# 02-MIC.net
KiCad netlist of a schematic drawn in Altium Designer
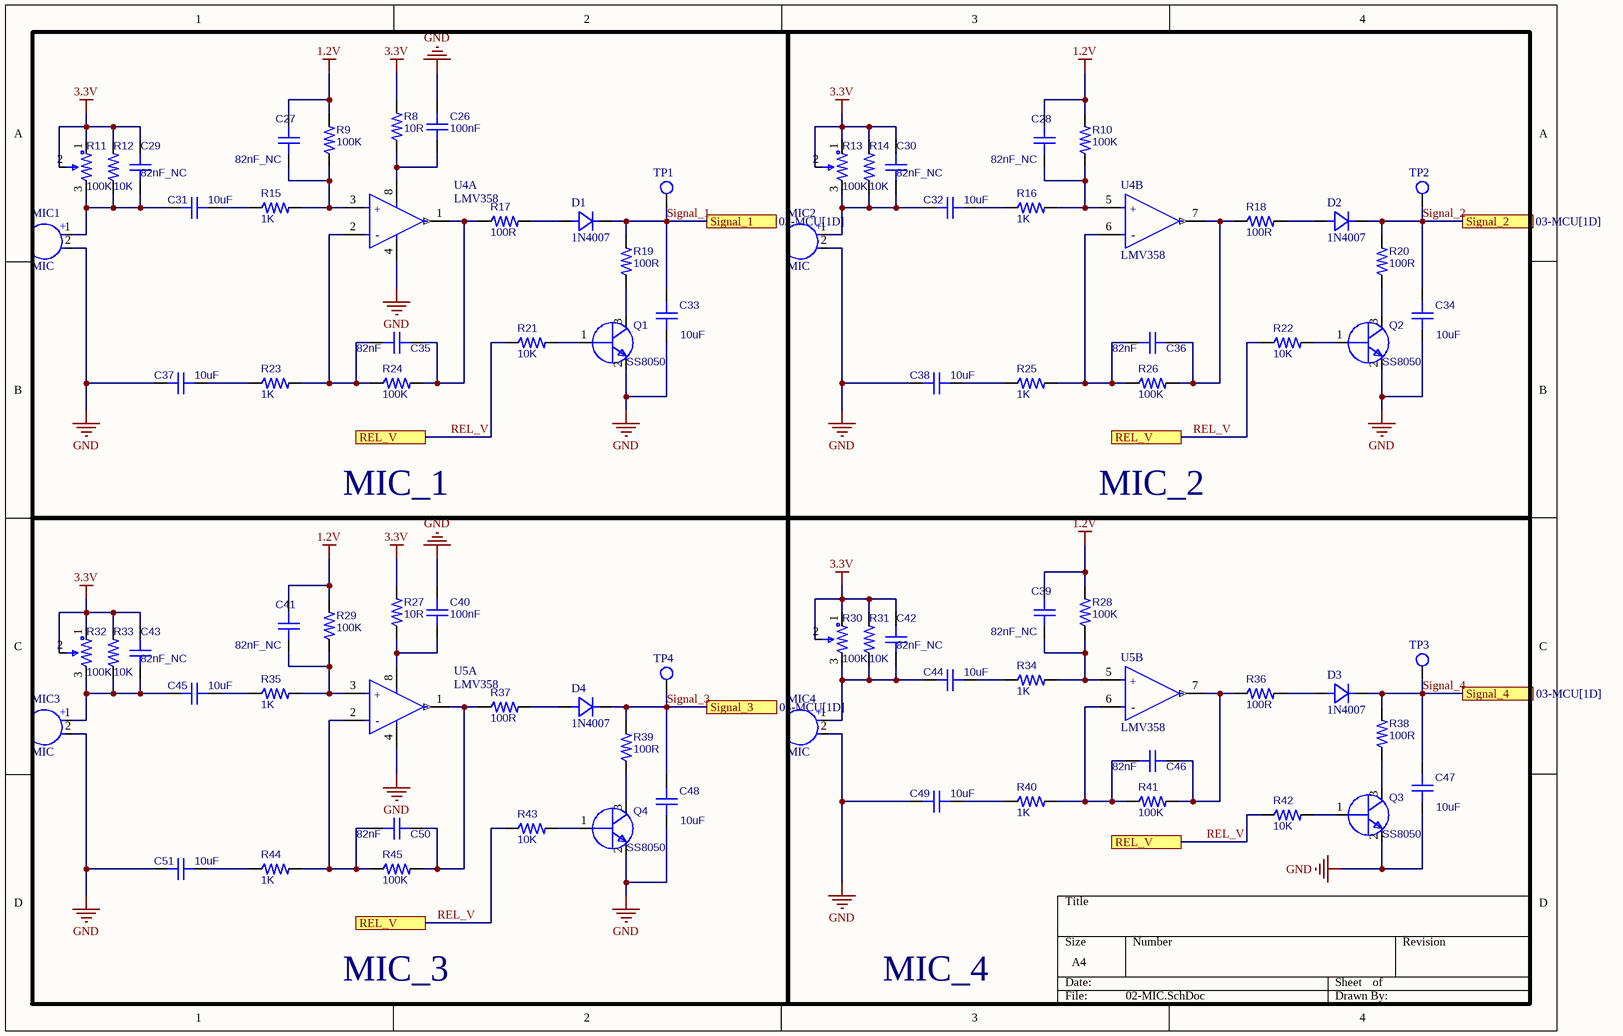
[diagram p0: 02-MIC.SchDoc]

(export (version "E")
  (design (tool "Eeschema 10.0.6"))
  (components
    (comp (ref "C26")
      (value "100nF")
      (footprint "CAP-SMD-0603")
      (description "贴片电容")
      (fields
        (field (name "BOM_MANUFACTURER PART") "CL03A104KQ3NNNC")
        (field (name "BOM_SUPPLIER PART") "C160831")
        (field (name "CONTRIBUTOR") "LCSC")
      )
      (libsource (lib "声源跟踪小车原理图库") (part "CAP"))
    )
    (comp (ref "C27")
      (value "82nF_NC")
      (footprint "CAP-SMD-0603")
      (description "贴片电容")
      (fields
        (field (name "BOM_MANUFACTURER PART") "CL03A104KQ3NNNC")
        (field (name "BOM_SUPPLIER PART") "C160831")
        (field (name "CONTRIBUTOR") "LCSC")
      )
      (libsource (lib "声源跟踪小车原理图库") (part "CAP"))
    )
    (comp (ref "C28")
      (value "82nF_NC")
      (footprint "CAP-SMD-0603")
      (description "贴片电容")
      (fields
        (field (name "BOM_MANUFACTURER PART") "CL03A104KQ3NNNC")
        (field (name "BOM_SUPPLIER PART") "C160831")
        (field (name "CONTRIBUTOR") "LCSC")
      )
      (libsource (lib "声源跟踪小车原理图库") (part "CAP"))
    )
    (comp (ref "C29")
      (value "82nF_NC")
      (footprint "CAP-SMD-0603")
      (description "贴片电容")
      (fields
        (field (name "BOM_MANUFACTURER PART") "CL03A104KQ3NNNC")
        (field (name "BOM_SUPPLIER PART") "C160831")
        (field (name "CONTRIBUTOR") "LCSC")
      )
      (libsource (lib "声源跟踪小车原理图库") (part "CAP"))
    )
    (comp (ref "C30")
      (value "82nF_NC")
      (footprint "CAP-SMD-0603")
      (description "贴片电容")
      (fields
        (field (name "BOM_MANUFACTURER PART") "CL03A104KQ3NNNC")
        (field (name "BOM_SUPPLIER PART") "C160831")
        (field (name "CONTRIBUTOR") "LCSC")
      )
      (libsource (lib "声源跟踪小车原理图库") (part "CAP"))
    )
    (comp (ref "C31")
      (value "10uF")
      (footprint "CAP-SMD-0603")
      (description "贴片电容")
      (fields
        (field (name "BOM_MANUFACTURER PART") "CL03A104KQ3NNNC")
        (field (name "BOM_SUPPLIER PART") "C160831")
        (field (name "CONTRIBUTOR") "LCSC")
      )
      (libsource (lib "声源跟踪小车原理图库") (part "CAP"))
    )
    (comp (ref "C32")
      (value "10uF")
      (footprint "CAP-SMD-0603")
      (description "贴片电容")
      (fields
        (field (name "BOM_MANUFACTURER PART") "CL03A104KQ3NNNC")
        (field (name "BOM_SUPPLIER PART") "C160831")
        (field (name "CONTRIBUTOR") "LCSC")
      )
      (libsource (lib "声源跟踪小车原理图库") (part "CAP"))
    )
    (comp (ref "C33")
      (value "10uF")
      (footprint "CAP-SMD-0603")
      (description "贴片电容")
      (fields
        (field (name "BOM_MANUFACTURER PART") "CL03A104KQ3NNNC")
        (field (name "BOM_SUPPLIER PART") "C160831")
        (field (name "CONTRIBUTOR") "LCSC")
      )
      (libsource (lib "声源跟踪小车原理图库") (part "CAP"))
    )
    (comp (ref "C34")
      (value "10uF")
      (footprint "CAP-SMD-0603")
      (description "贴片电容")
      (fields
        (field (name "BOM_MANUFACTURER PART") "CL03A104KQ3NNNC")
        (field (name "BOM_SUPPLIER PART") "C160831")
        (field (name "CONTRIBUTOR") "LCSC")
      )
      (libsource (lib "声源跟踪小车原理图库") (part "CAP"))
    )
    (comp (ref "C35")
      (value "82nF")
      (footprint "CAP-SMD-0603")
      (description "贴片电容")
      (fields
        (field (name "BOM_MANUFACTURER PART") "CL03A104KQ3NNNC")
        (field (name "BOM_SUPPLIER PART") "C160831")
        (field (name "CONTRIBUTOR") "LCSC")
      )
      (libsource (lib "声源跟踪小车原理图库") (part "CAP"))
    )
    (comp (ref "C36")
      (value "82nF")
      (footprint "CAP-SMD-0603")
      (description "贴片电容")
      (fields
        (field (name "BOM_MANUFACTURER PART") "CL03A104KQ3NNNC")
        (field (name "BOM_SUPPLIER PART") "C160831")
        (field (name "CONTRIBUTOR") "LCSC")
      )
      (libsource (lib "声源跟踪小车原理图库") (part "CAP"))
    )
    (comp (ref "C37")
      (value "10uF")
      (footprint "CAP-SMD-0603")
      (description "贴片电容")
      (fields
        (field (name "BOM_MANUFACTURER PART") "CL03A104KQ3NNNC")
        (field (name "BOM_SUPPLIER PART") "C160831")
        (field (name "CONTRIBUTOR") "LCSC")
      )
      (libsource (lib "声源跟踪小车原理图库") (part "CAP"))
    )
    (comp (ref "C38")
      (value "10uF")
      (footprint "CAP-SMD-0603")
      (description "贴片电容")
      (fields
        (field (name "BOM_MANUFACTURER PART") "CL03A104KQ3NNNC")
        (field (name "BOM_SUPPLIER PART") "C160831")
        (field (name "CONTRIBUTOR") "LCSC")
      )
      (libsource (lib "声源跟踪小车原理图库") (part "CAP"))
    )
    (comp (ref "C39")
      (value "82nF_NC")
      (footprint "CAP-SMD-0603")
      (description "贴片电容")
      (fields
        (field (name "BOM_MANUFACTURER PART") "CL03A104KQ3NNNC")
        (field (name "BOM_SUPPLIER PART") "C160831")
        (field (name "CONTRIBUTOR") "LCSC")
      )
      (libsource (lib "声源跟踪小车原理图库") (part "CAP"))
    )
    (comp (ref "C40")
      (value "100nF")
      (footprint "CAP-SMD-0603")
      (description "贴片电容")
      (fields
        (field (name "BOM_MANUFACTURER PART") "CL03A104KQ3NNNC")
        (field (name "BOM_SUPPLIER PART") "C160831")
        (field (name "CONTRIBUTOR") "LCSC")
      )
      (libsource (lib "声源跟踪小车原理图库") (part "CAP"))
    )
    (comp (ref "C41")
      (value "82nF_NC")
      (footprint "CAP-SMD-0603")
      (description "贴片电容")
      (fields
        (field (name "BOM_MANUFACTURER PART") "CL03A104KQ3NNNC")
        (field (name "BOM_SUPPLIER PART") "C160831")
        (field (name "CONTRIBUTOR") "LCSC")
      )
      (libsource (lib "声源跟踪小车原理图库") (part "CAP"))
    )
    (comp (ref "C42")
      (value "82nF_NC")
      (footprint "CAP-SMD-0603")
      (description "贴片电容")
      (fields
        (field (name "BOM_MANUFACTURER PART") "CL03A104KQ3NNNC")
        (field (name "BOM_SUPPLIER PART") "C160831")
        (field (name "CONTRIBUTOR") "LCSC")
      )
      (libsource (lib "声源跟踪小车原理图库") (part "CAP"))
    )
    (comp (ref "C43")
      (value "82nF_NC")
      (footprint "CAP-SMD-0603")
      (description "贴片电容")
      (fields
        (field (name "BOM_MANUFACTURER PART") "CL03A104KQ3NNNC")
        (field (name "BOM_SUPPLIER PART") "C160831")
        (field (name "CONTRIBUTOR") "LCSC")
      )
      (libsource (lib "声源跟踪小车原理图库") (part "CAP"))
    )
    (comp (ref "C44")
      (value "10uF")
      (footprint "CAP-SMD-0603")
      (description "贴片电容")
      (fields
        (field (name "BOM_MANUFACTURER PART") "CL03A104KQ3NNNC")
        (field (name "BOM_SUPPLIER PART") "C160831")
        (field (name "CONTRIBUTOR") "LCSC")
      )
      (libsource (lib "声源跟踪小车原理图库") (part "CAP"))
    )
    (comp (ref "C45")
      (value "10uF")
      (footprint "CAP-SMD-0603")
      (description "贴片电容")
      (fields
        (field (name "BOM_MANUFACTURER PART") "CL03A104KQ3NNNC")
        (field (name "BOM_SUPPLIER PART") "C160831")
        (field (name "CONTRIBUTOR") "LCSC")
      )
      (libsource (lib "声源跟踪小车原理图库") (part "CAP"))
    )
    (comp (ref "C46")
      (value "82nF")
      (footprint "CAP-SMD-0603")
      (description "贴片电容")
      (fields
        (field (name "BOM_MANUFACTURER PART") "CL03A104KQ3NNNC")
        (field (name "BOM_SUPPLIER PART") "C160831")
        (field (name "CONTRIBUTOR") "LCSC")
      )
      (libsource (lib "声源跟踪小车原理图库") (part "CAP"))
    )
    (comp (ref "C47")
      (value "10uF")
      (footprint "CAP-SMD-0603")
      (description "贴片电容")
      (fields
        (field (name "BOM_MANUFACTURER PART") "CL03A104KQ3NNNC")
        (field (name "BOM_SUPPLIER PART") "C160831")
        (field (name "CONTRIBUTOR") "LCSC")
      )
      (libsource (lib "声源跟踪小车原理图库") (part "CAP"))
    )
    (comp (ref "C48")
      (value "10uF")
      (footprint "CAP-SMD-0603")
      (description "贴片电容")
      (fields
        (field (name "BOM_MANUFACTURER PART") "CL03A104KQ3NNNC")
        (field (name "BOM_SUPPLIER PART") "C160831")
        (field (name "CONTRIBUTOR") "LCSC")
      )
      (libsource (lib "声源跟踪小车原理图库") (part "CAP"))
    )
    (comp (ref "C49")
      (value "10uF")
      (footprint "CAP-SMD-0603")
      (description "贴片电容")
      (fields
        (field (name "BOM_MANUFACTURER PART") "CL03A104KQ3NNNC")
        (field (name "BOM_SUPPLIER PART") "C160831")
        (field (name "CONTRIBUTOR") "LCSC")
      )
      (libsource (lib "声源跟踪小车原理图库") (part "CAP"))
    )
    (comp (ref "C50")
      (value "82nF")
      (footprint "CAP-SMD-0603")
      (description "贴片电容")
      (fields
        (field (name "BOM_MANUFACTURER PART") "CL03A104KQ3NNNC")
        (field (name "BOM_SUPPLIER PART") "C160831")
        (field (name "CONTRIBUTOR") "LCSC")
      )
      (libsource (lib "声源跟踪小车原理图库") (part "CAP"))
    )
    (comp (ref "C51")
      (value "10uF")
      (footprint "CAP-SMD-0603")
      (description "贴片电容")
      (fields
        (field (name "BOM_MANUFACTURER PART") "CL03A104KQ3NNNC")
        (field (name "BOM_SUPPLIER PART") "C160831")
        (field (name "CONTRIBUTOR") "LCSC")
      )
      (libsource (lib "声源跟踪小车原理图库") (part "CAP"))
    )
    (comp (ref "D1")
      (value "1N4007")
      (footprint "SOD-123-P3.4")
      (description "二极管1N4148W")
      (fields (field (name "MANUFACTURER") "PSI(宝力芯)") (field (name "MANUFACTURER PART") "1N4148W"))
      (libsource (lib "声源跟踪小车原理图库") (part "Diode"))
    )
    (comp (ref "D2")
      (value "1N4007")
      (footprint "SOD-123-P3.4")
      (description "二极管1N4148W")
      (fields (field (name "MANUFACTURER") "PSI(宝力芯)") (field (name "MANUFACTURER PART") "1N4148W"))
      (libsource (lib "声源跟踪小车原理图库") (part "Diode"))
    )
    (comp (ref "D3")
      (value "1N4007")
      (footprint "SOD-123-P3.4")
      (description "二极管1N4148W")
      (fields (field (name "MANUFACTURER") "PSI(宝力芯)") (field (name "MANUFACTURER PART") "1N4148W"))
      (libsource (lib "声源跟踪小车原理图库") (part "Diode"))
    )
    (comp (ref "D4")
      (value "1N4007")
      (footprint "SOD-123-P3.4")
      (description "二极管1N4148W")
      (fields (field (name "MANUFACTURER") "PSI(宝力芯)") (field (name "MANUFACTURER PART") "1N4148W"))
      (libsource (lib "声源跟踪小车原理图库") (part "Diode"))
    )
    (comp (ref "MIC1")
      (value "MIC")
      (footprint "CONN-TH-1X2P-P2.54_2")
      (description "咪头MIC COND ANALOG OMNI -38DB")
      (libsource (lib "声源跟踪小车原理图库") (part "MIC"))
    )
    (comp (ref "MIC2")
      (value "MIC")
      (footprint "CONN-TH-1X2P-P2.54_2")
      (description "咪头MIC COND ANALOG OMNI -38DB")
      (libsource (lib "声源跟踪小车原理图库") (part "MIC"))
    )
    (comp (ref "MIC3")
      (value "MIC")
      (footprint "CONN-TH-1X2P-P2.54_2")
      (description "咪头MIC COND ANALOG OMNI -38DB")
      (libsource (lib "声源跟踪小车原理图库") (part "MIC"))
    )
    (comp (ref "MIC4")
      (value "MIC")
      (footprint "CONN-TH-1X2P-P2.54_2")
      (description "咪头MIC COND ANALOG OMNI -38DB")
      (libsource (lib "声源跟踪小车原理图库") (part "MIC"))
    )
    (comp (ref "Q1")
      (value "SS8050")
      (footprint "SOT-23-3-LP2.28-P1.91")
      (description "贴片NPN三极管")
      (fields
        (field (name "BOM_SUPPLIER PART") "C2898668")
        (field (name "BOM_MANUFACTURER PART") "S9013")
        (field (name "CONTRIBUTOR") "LCSC")
      )
      (libsource (lib "声源跟踪小车原理图库") (part "NPN-SOT-23-3"))
    )
    (comp (ref "Q2")
      (value "SS8050")
      (footprint "SOT-23-3-LP2.28-P1.91")
      (description "贴片NPN三极管")
      (fields
        (field (name "BOM_SUPPLIER PART") "C2898668")
        (field (name "BOM_MANUFACTURER PART") "S9013")
        (field (name "CONTRIBUTOR") "LCSC")
      )
      (libsource (lib "声源跟踪小车原理图库") (part "NPN-SOT-23-3"))
    )
    (comp (ref "Q3")
      (value "SS8050")
      (footprint "SOT-23-3-LP2.28-P1.91")
      (description "贴片NPN三极管")
      (fields
        (field (name "BOM_SUPPLIER PART") "C2898668")
        (field (name "BOM_MANUFACTURER PART") "S9013")
        (field (name "CONTRIBUTOR") "LCSC")
      )
      (libsource (lib "声源跟踪小车原理图库") (part "NPN-SOT-23-3"))
    )
    (comp (ref "Q4")
      (value "SS8050")
      (footprint "SOT-23-3-LP2.28-P1.91")
      (description "贴片NPN三极管")
      (fields
        (field (name "BOM_SUPPLIER PART") "C2898668")
        (field (name "BOM_MANUFACTURER PART") "S9013")
        (field (name "CONTRIBUTOR") "LCSC")
      )
      (libsource (lib "声源跟踪小车原理图库") (part "NPN-SOT-23-3"))
    )
    (comp (ref "R8")
      (value "10R")
      (footprint "RES-SMD-0603")
      (description "贴片电阻")
      (fields
        (field (name "BOM_SUPPLIER PART") "C118966")
        (field (name "BOM_MANUFACTURER PART") "3362P-1-104")
        (field (name "CONTRIBUTOR") "LCSC")
      )
      (libsource (lib "声源跟踪小车原理图库") (part "RES"))
    )
    (comp (ref "R9")
      (value "100K")
      (footprint "RES-SMD-0603")
      (description "贴片电阻")
      (fields
        (field (name "BOM_SUPPLIER PART") "C118966")
        (field (name "BOM_MANUFACTURER PART") "3362P-1-104")
        (field (name "CONTRIBUTOR") "LCSC")
      )
      (libsource (lib "声源跟踪小车原理图库") (part "RES"))
    )
    (comp (ref "R10")
      (value "100K")
      (footprint "RES-SMD-0603")
      (description "贴片电阻")
      (fields
        (field (name "BOM_SUPPLIER PART") "C118966")
        (field (name "BOM_MANUFACTURER PART") "3362P-1-104")
        (field (name "CONTRIBUTOR") "LCSC")
      )
      (libsource (lib "声源跟踪小车原理图库") (part "RES"))
    )
    (comp (ref "R11")
      (value "100K")
      (footprint "RES-TH-ADJ-3396W")
      (description "可调电阻,电位器")
      (fields
        (field (name "BOM_SUPPLIER PART") "C118966")
        (field (name "BOM_MANUFACTURER PART") "3362P-1-104")
        (field (name "CONTRIBUTOR") "LCSC")
      )
      (libsource (lib "声源跟踪小车原理图库") (part "RES-ADJ"))
    )
    (comp (ref "R12")
      (value "10K")
      (footprint "RES-SMD-0603")
      (description "贴片电阻")
      (fields
        (field (name "BOM_SUPPLIER PART") "C118966")
        (field (name "BOM_MANUFACTURER PART") "3362P-1-104")
        (field (name "CONTRIBUTOR") "LCSC")
      )
      (libsource (lib "声源跟踪小车原理图库") (part "RES"))
    )
    (comp (ref "R13")
      (value "100K")
      (footprint "RES-TH-ADJ-3396W")
      (description "可调电阻,电位器")
      (fields
        (field (name "BOM_SUPPLIER PART") "C118966")
        (field (name "BOM_MANUFACTURER PART") "3362P-1-104")
        (field (name "CONTRIBUTOR") "LCSC")
      )
      (libsource (lib "声源跟踪小车原理图库") (part "RES-ADJ"))
    )
    (comp (ref "R14")
      (value "10K")
      (footprint "RES-SMD-0603")
      (description "贴片电阻")
      (fields
        (field (name "BOM_SUPPLIER PART") "C118966")
        (field (name "BOM_MANUFACTURER PART") "3362P-1-104")
        (field (name "CONTRIBUTOR") "LCSC")
      )
      (libsource (lib "声源跟踪小车原理图库") (part "RES"))
    )
    (comp (ref "R15")
      (value "1K")
      (footprint "RES-SMD-0603")
      (description "贴片电阻")
      (fields
        (field (name "BOM_SUPPLIER PART") "C118966")
        (field (name "BOM_MANUFACTURER PART") "3362P-1-104")
        (field (name "CONTRIBUTOR") "LCSC")
      )
      (libsource (lib "声源跟踪小车原理图库") (part "RES"))
    )
    (comp (ref "R16")
      (value "1K")
      (footprint "RES-SMD-0603")
      (description "贴片电阻")
      (fields
        (field (name "BOM_SUPPLIER PART") "C118966")
        (field (name "BOM_MANUFACTURER PART") "3362P-1-104")
        (field (name "CONTRIBUTOR") "LCSC")
      )
      (libsource (lib "声源跟踪小车原理图库") (part "RES"))
    )
    (comp (ref "R17")
      (value "100R")
      (footprint "RES-SMD-0603")
      (description "贴片电阻")
      (fields
        (field (name "BOM_SUPPLIER PART") "C118966")
        (field (name "BOM_MANUFACTURER PART") "3362P-1-104")
        (field (name "CONTRIBUTOR") "LCSC")
      )
      (libsource (lib "声源跟踪小车原理图库") (part "RES"))
    )
    (comp (ref "R18")
      (value "100R")
      (footprint "RES-SMD-0603")
      (description "贴片电阻")
      (fields
        (field (name "BOM_SUPPLIER PART") "C118966")
        (field (name "BOM_MANUFACTURER PART") "3362P-1-104")
        (field (name "CONTRIBUTOR") "LCSC")
      )
      (libsource (lib "声源跟踪小车原理图库") (part "RES"))
    )
    (comp (ref "R19")
      (value "100R")
      (footprint "RES-SMD-0603")
      (description "贴片电阻")
      (fields
        (field (name "BOM_SUPPLIER PART") "C118966")
        (field (name "BOM_MANUFACTURER PART") "3362P-1-104")
        (field (name "CONTRIBUTOR") "LCSC")
      )
      (libsource (lib "声源跟踪小车原理图库") (part "RES"))
    )
    (comp (ref "R20")
      (value "100R")
      (footprint "RES-SMD-0603")
      (description "贴片电阻")
      (fields
        (field (name "BOM_SUPPLIER PART") "C118966")
        (field (name "BOM_MANUFACTURER PART") "3362P-1-104")
        (field (name "CONTRIBUTOR") "LCSC")
      )
      (libsource (lib "声源跟踪小车原理图库") (part "RES"))
    )
    (comp (ref "R21")
      (value "10K")
      (footprint "RES-SMD-0603")
      (description "贴片电阻")
      (fields
        (field (name "BOM_SUPPLIER PART") "C118966")
        (field (name "BOM_MANUFACTURER PART") "3362P-1-104")
        (field (name "CONTRIBUTOR") "LCSC")
      )
      (libsource (lib "声源跟踪小车原理图库") (part "RES"))
    )
    (comp (ref "R22")
      (value "10K")
      (footprint "RES-SMD-0603")
      (description "贴片电阻")
      (fields
        (field (name "BOM_SUPPLIER PART") "C118966")
        (field (name "BOM_MANUFACTURER PART") "3362P-1-104")
        (field (name "CONTRIBUTOR") "LCSC")
      )
      (libsource (lib "声源跟踪小车原理图库") (part "RES"))
    )
    (comp (ref "R23")
      (value "1K")
      (footprint "RES-SMD-0603")
      (description "贴片电阻")
      (fields
        (field (name "BOM_SUPPLIER PART") "C118966")
        (field (name "BOM_MANUFACTURER PART") "3362P-1-104")
        (field (name "CONTRIBUTOR") "LCSC")
      )
      (libsource (lib "声源跟踪小车原理图库") (part "RES"))
    )
    (comp (ref "R24")
      (value "100K")
      (footprint "RES-SMD-0603")
      (description "贴片电阻")
      (fields
        (field (name "BOM_SUPPLIER PART") "C118966")
        (field (name "BOM_MANUFACTURER PART") "3362P-1-104")
        (field (name "CONTRIBUTOR") "LCSC")
      )
      (libsource (lib "声源跟踪小车原理图库") (part "RES"))
    )
    (comp (ref "R25")
      (value "1K")
      (footprint "RES-SMD-0603")
      (description "贴片电阻")
      (fields
        (field (name "BOM_SUPPLIER PART") "C118966")
        (field (name "BOM_MANUFACTURER PART") "3362P-1-104")
        (field (name "CONTRIBUTOR") "LCSC")
      )
      (libsource (lib "声源跟踪小车原理图库") (part "RES"))
    )
    (comp (ref "R26")
      (value "100K")
      (footprint "RES-SMD-0603")
      (description "贴片电阻")
      (fields
        (field (name "BOM_SUPPLIER PART") "C118966")
        (field (name "BOM_MANUFACTURER PART") "3362P-1-104")
        (field (name "CONTRIBUTOR") "LCSC")
      )
      (libsource (lib "声源跟踪小车原理图库") (part "RES"))
    )
    (comp (ref "R27")
      (value "10R")
      (footprint "RES-SMD-0603")
      (description "贴片电阻")
      (fields
        (field (name "BOM_SUPPLIER PART") "C118966")
        (field (name "BOM_MANUFACTURER PART") "3362P-1-104")
        (field (name "CONTRIBUTOR") "LCSC")
      )
      (libsource (lib "声源跟踪小车原理图库") (part "RES"))
    )
    (comp (ref "R28")
      (value "100K")
      (footprint "RES-SMD-0603")
      (description "贴片电阻")
      (fields
        (field (name "BOM_SUPPLIER PART") "C118966")
        (field (name "BOM_MANUFACTURER PART") "3362P-1-104")
        (field (name "CONTRIBUTOR") "LCSC")
      )
      (libsource (lib "声源跟踪小车原理图库") (part "RES"))
    )
    (comp (ref "R29")
      (value "100K")
      (footprint "RES-SMD-0603")
      (description "贴片电阻")
      (fields
        (field (name "BOM_SUPPLIER PART") "C118966")
        (field (name "BOM_MANUFACTURER PART") "3362P-1-104")
        (field (name "CONTRIBUTOR") "LCSC")
      )
      (libsource (lib "声源跟踪小车原理图库") (part "RES"))
    )
    (comp (ref "R30")
      (value "100K")
      (footprint "RES-TH-ADJ-3396W")
      (description "可调电阻,电位器")
      (fields
        (field (name "BOM_SUPPLIER PART") "C118966")
        (field (name "BOM_MANUFACTURER PART") "3362P-1-104")
        (field (name "CONTRIBUTOR") "LCSC")
      )
      (libsource (lib "声源跟踪小车原理图库") (part "RES-ADJ"))
    )
    (comp (ref "R31")
      (value "10K")
      (footprint "RES-SMD-0603")
      (description "贴片电阻")
      (fields
        (field (name "BOM_SUPPLIER PART") "C118966")
        (field (name "BOM_MANUFACTURER PART") "3362P-1-104")
        (field (name "CONTRIBUTOR") "LCSC")
      )
      (libsource (lib "声源跟踪小车原理图库") (part "RES"))
    )
    (comp (ref "R32")
      (value "100K")
      (footprint "RES-TH-ADJ-3396W")
      (description "可调电阻,电位器")
      (fields
        (field (name "BOM_SUPPLIER PART") "C118966")
        (field (name "BOM_MANUFACTURER PART") "3362P-1-104")
        (field (name "CONTRIBUTOR") "LCSC")
      )
      (libsource (lib "声源跟踪小车原理图库") (part "RES-ADJ"))
    )
    (comp (ref "R33")
      (value "10K")
      (footprint "RES-SMD-0603")
      (description "贴片电阻")
      (fields
        (field (name "BOM_SUPPLIER PART") "C118966")
        (field (name "BOM_MANUFACTURER PART") "3362P-1-104")
        (field (name "CONTRIBUTOR") "LCSC")
      )
      (libsource (lib "声源跟踪小车原理图库") (part "RES"))
    )
    (comp (ref "R34")
      (value "1K")
      (footprint "RES-SMD-0603")
      (description "贴片电阻")
      (fields
        (field (name "BOM_SUPPLIER PART") "C118966")
        (field (name "BOM_MANUFACTURER PART") "3362P-1-104")
        (field (name "CONTRIBUTOR") "LCSC")
      )
      (libsource (lib "声源跟踪小车原理图库") (part "RES"))
    )
    (comp (ref "R35")
      (value "1K")
      (footprint "RES-SMD-0603")
      (description "贴片电阻")
      (fields
        (field (name "BOM_SUPPLIER PART") "C118966")
        (field (name "BOM_MANUFACTURER PART") "3362P-1-104")
        (field (name "CONTRIBUTOR") "LCSC")
      )
      (libsource (lib "声源跟踪小车原理图库") (part "RES"))
    )
    (comp (ref "R36")
      (value "100R")
      (footprint "RES-SMD-0603")
      (description "贴片电阻")
      (fields
        (field (name "BOM_SUPPLIER PART") "C118966")
        (field (name "BOM_MANUFACTURER PART") "3362P-1-104")
        (field (name "CONTRIBUTOR") "LCSC")
      )
      (libsource (lib "声源跟踪小车原理图库") (part "RES"))
    )
    (comp (ref "R37")
      (value "100R")
      (footprint "RES-SMD-0603")
      (description "贴片电阻")
      (fields
        (field (name "BOM_SUPPLIER PART") "C118966")
        (field (name "BOM_MANUFACTURER PART") "3362P-1-104")
        (field (name "CONTRIBUTOR") "LCSC")
      )
      (libsource (lib "声源跟踪小车原理图库") (part "RES"))
    )
    (comp (ref "R38")
      (value "100R")
      (footprint "RES-SMD-0603")
      (description "贴片电阻")
      (fields
        (field (name "BOM_SUPPLIER PART") "C118966")
        (field (name "BOM_MANUFACTURER PART") "3362P-1-104")
        (field (name "CONTRIBUTOR") "LCSC")
      )
      (libsource (lib "声源跟踪小车原理图库") (part "RES"))
    )
    (comp (ref "R39")
      (value "100R")
      (footprint "RES-SMD-0603")
      (description "贴片电阻")
      (fields
        (field (name "BOM_SUPPLIER PART") "C118966")
        (field (name "BOM_MANUFACTURER PART") "3362P-1-104")
        (field (name "CONTRIBUTOR") "LCSC")
      )
      (libsource (lib "声源跟踪小车原理图库") (part "RES"))
    )
    (comp (ref "R40")
      (value "1K")
      (footprint "RES-SMD-0603")
      (description "贴片电阻")
      (fields
        (field (name "BOM_SUPPLIER PART") "C118966")
        (field (name "BOM_MANUFACTURER PART") "3362P-1-104")
        (field (name "CONTRIBUTOR") "LCSC")
      )
      (libsource (lib "声源跟踪小车原理图库") (part "RES"))
    )
    (comp (ref "R41")
      (value "100K")
      (footprint "RES-SMD-0603")
      (description "贴片电阻")
      (fields
        (field (name "BOM_SUPPLIER PART") "C118966")
        (field (name "BOM_MANUFACTURER PART") "3362P-1-104")
        (field (name "CONTRIBUTOR") "LCSC")
      )
      (libsource (lib "声源跟踪小车原理图库") (part "RES"))
    )
    (comp (ref "R42")
      (value "10K")
      (footprint "RES-SMD-0603")
      (description "贴片电阻")
      (fields
        (field (name "BOM_SUPPLIER PART") "C118966")
        (field (name "BOM_MANUFACTURER PART") "3362P-1-104")
        (field (name "CONTRIBUTOR") "LCSC")
      )
      (libsource (lib "声源跟踪小车原理图库") (part "RES"))
    )
    (comp (ref "R43")
      (value "10K")
      (footprint "RES-SMD-0603")
      (description "贴片电阻")
      (fields
        (field (name "BOM_SUPPLIER PART") "C118966")
        (field (name "BOM_MANUFACTURER PART") "3362P-1-104")
        (field (name "CONTRIBUTOR") "LCSC")
      )
      (libsource (lib "声源跟踪小车原理图库") (part "RES"))
    )
    (comp (ref "R44")
      (value "1K")
      (footprint "RES-SMD-0603")
      (description "贴片电阻")
      (fields
        (field (name "BOM_SUPPLIER PART") "C118966")
        (field (name "BOM_MANUFACTURER PART") "3362P-1-104")
        (field (name "CONTRIBUTOR") "LCSC")
      )
      (libsource (lib "声源跟踪小车原理图库") (part "RES"))
    )
    (comp (ref "R45")
      (value "100K")
      (footprint "RES-SMD-0603")
      (description "贴片电阻")
      (fields
        (field (name "BOM_SUPPLIER PART") "C118966")
        (field (name "BOM_MANUFACTURER PART") "3362P-1-104")
        (field (name "CONTRIBUTOR") "LCSC")
      )
      (libsource (lib "声源跟踪小车原理图库") (part "RES"))
    )
    (comp (ref "TP1")
      (value "TP")
      (footprint "TP")
      (description "TP测试点")
      (libsource (lib "声源跟踪小车原理图库") (part "TP"))
    )
    (comp (ref "TP2")
      (value "TP")
      (footprint "TP")
      (description "TP测试点")
      (libsource (lib "声源跟踪小车原理图库") (part "TP"))
    )
    (comp (ref "TP3")
      (value "TP")
      (footprint "TP")
      (description "TP测试点")
      (libsource (lib "声源跟踪小车原理图库") (part "TP"))
    )
    (comp (ref "TP4")
      (value "TP")
      (footprint "TP")
      (description "TP测试点")
      (libsource (lib "声源跟踪小车原理图库") (part "TP"))
    )
    (comp (ref "U4")
      (value "LMV358")
      (footprint "SOIC-8-LP5.5-P1.27")
      (description "运放IC OPAMP GP 2 CIRCUIT 8SOIC")
      (libsource (lib "声源跟踪小车原理图库") (part "LMV358"))
    )
    (comp (ref "U5")
      (value "LMV358")
      (footprint "SOIC-8-LP5.5-P1.27")
      (description "运放IC OPAMP GP 2 CIRCUIT 8SOIC")
      (libsource (lib "声源跟踪小车原理图库") (part "LMV358"))
    )
  )
  (nets
    (net (code "1") (name "/REL_V") (class "Default")
      (node (ref "R21") (pin "1") (pinfunction "1_1") (pintype "passive"))
      (node (ref "R22") (pin "1") (pinfunction "1_1") (pintype "passive"))
      (node (ref "R42") (pin "1") (pinfunction "1_1") (pintype "passive"))
      (node (ref "R43") (pin "1") (pinfunction "1_1") (pintype "passive"))
    )
    (net (code "2") (name "/Signal_1") (class "Default")
      (node (ref "C33") (pin "2") (pinfunction "2_2") (pintype "passive"))
      (node (ref "D1") (pin "2") (pinfunction "A_2") (pintype "passive"))
      (node (ref "R19") (pin "2") (pinfunction "2_2") (pintype "passive"))
      (node (ref "TP1") (pin "1") (pinfunction "1_1") (pintype "passive"))
    )
    (net (code "3") (name "/Signal_2") (class "Default")
      (node (ref "C34") (pin "2") (pinfunction "2_2") (pintype "passive"))
      (node (ref "D2") (pin "2") (pinfunction "A_2") (pintype "passive"))
      (node (ref "R20") (pin "2") (pinfunction "2_2") (pintype "passive"))
      (node (ref "TP2") (pin "1") (pinfunction "1_1") (pintype "passive"))
    )
    (net (code "4") (name "/Signal_3") (class "Default")
      (node (ref "C48") (pin "2") (pinfunction "2_2") (pintype "passive"))
      (node (ref "D4") (pin "2") (pinfunction "A_2") (pintype "passive"))
      (node (ref "R39") (pin "2") (pinfunction "2_2") (pintype "passive"))
      (node (ref "TP4") (pin "1") (pinfunction "1_1") (pintype "passive"))
    )
    (net (code "5") (name "/Signal_4") (class "Default")
      (node (ref "C47") (pin "2") (pinfunction "2_2") (pintype "passive"))
      (node (ref "D3") (pin "2") (pinfunction "A_2") (pintype "passive"))
      (node (ref "R38") (pin "2") (pinfunction "2_2") (pintype "passive"))
      (node (ref "TP3") (pin "1") (pinfunction "1_1") (pintype "passive"))
    )
    (net (code "6") (name "1.2V") (class "Default")
      (node (ref "C27") (pin "2") (pinfunction "2_2") (pintype "passive"))
      (node (ref "C28") (pin "2") (pinfunction "2_2") (pintype "passive"))
      (node (ref "C39") (pin "2") (pinfunction "2_2") (pintype "passive"))
      (node (ref "C41") (pin "2") (pinfunction "2_2") (pintype "passive"))
      (node (ref "R10") (pin "2") (pinfunction "2_2") (pintype "passive"))
      (node (ref "R28") (pin "2") (pinfunction "2_2") (pintype "passive"))
      (node (ref "R29") (pin "2") (pinfunction "2_2") (pintype "passive"))
      (node (ref "R9") (pin "2") (pinfunction "2_2") (pintype "passive"))
    )
    (net (code "7") (name "3.3V") (class "Default")
      (node (ref "C29") (pin "2") (pinfunction "2_2") (pintype "passive"))
      (node (ref "C30") (pin "2") (pinfunction "2_2") (pintype "passive"))
      (node (ref "C42") (pin "2") (pinfunction "2_2") (pintype "passive"))
      (node (ref "C43") (pin "2") (pinfunction "2_2") (pintype "passive"))
      (node (ref "R11") (pin "1") (pinfunction "1_1") (pintype "passive"))
      (node (ref "R11") (pin "2") (pinfunction "2_2") (pintype "passive"))
      (node (ref "R12") (pin "2") (pinfunction "2_2") (pintype "passive"))
      (node (ref "R13") (pin "1") (pinfunction "1_1") (pintype "passive"))
      (node (ref "R13") (pin "2") (pinfunction "2_2") (pintype "passive"))
      (node (ref "R14") (pin "2") (pinfunction "2_2") (pintype "passive"))
      (node (ref "R27") (pin "2") (pinfunction "2_2") (pintype "passive"))
      (node (ref "R30") (pin "1") (pinfunction "1_1") (pintype "passive"))
      (node (ref "R30") (pin "2") (pinfunction "2_2") (pintype "passive"))
      (node (ref "R31") (pin "2") (pinfunction "2_2") (pintype "passive"))
      (node (ref "R32") (pin "1") (pinfunction "1_1") (pintype "passive"))
      (node (ref "R32") (pin "2") (pinfunction "2_2") (pintype "passive"))
      (node (ref "R33") (pin "2") (pinfunction "2_2") (pintype "passive"))
      (node (ref "R8") (pin "2") (pinfunction "2_2") (pintype "passive"))
    )
    (net (code "8") (name "GND") (class "Default")
      (node (ref "C26") (pin "2") (pinfunction "2_2") (pintype "passive"))
      (node (ref "C33") (pin "1") (pinfunction "1_1") (pintype "passive"))
      (node (ref "C34") (pin "1") (pinfunction "1_1") (pintype "passive"))
      (node (ref "C37") (pin "1") (pinfunction "1_1") (pintype "passive"))
      (node (ref "C38") (pin "1") (pinfunction "1_1") (pintype "passive"))
      (node (ref "C40") (pin "2") (pinfunction "2_2") (pintype "passive"))
      (node (ref "C47") (pin "1") (pinfunction "1_1") (pintype "passive"))
      (node (ref "C48") (pin "1") (pinfunction "1_1") (pintype "passive"))
      (node (ref "C49") (pin "1") (pinfunction "1_1") (pintype "passive"))
      (node (ref "C51") (pin "1") (pinfunction "1_1") (pintype "passive"))
      (node (ref "MIC1") (pin "2") (pinfunction "C_2") (pintype "passive"))
      (node (ref "MIC2") (pin "2") (pinfunction "C_2") (pintype "passive"))
      (node (ref "MIC3") (pin "2") (pinfunction "C_2") (pintype "passive"))
      (node (ref "MIC4") (pin "2") (pinfunction "C_2") (pintype "passive"))
      (node (ref "Q1") (pin "2") (pinfunction "E_2") (pintype "passive"))
      (node (ref "Q2") (pin "2") (pinfunction "E_2") (pintype "passive"))
      (node (ref "Q3") (pin "2") (pinfunction "E_2") (pintype "passive"))
      (node (ref "Q4") (pin "2") (pinfunction "E_2") (pintype "passive"))
      (node (ref "U4") (pin "4") (pinfunction "GND_4") (pintype "power_in"))
      (node (ref "U5") (pin "4") (pinfunction "GND_4") (pintype "power_in"))
    )
    (net (code "9") (name "Net-(C31-Pad2)") (class "Default")
      (node (ref "C31") (pin "2") (pinfunction "2_2") (pintype "passive"))
      (node (ref "R15") (pin "1") (pinfunction "1_1") (pintype "passive"))
    )
    (net (code "10") (name "Net-(C32-Pad2)") (class "Default")
      (node (ref "C32") (pin "2") (pinfunction "2_2") (pintype "passive"))
      (node (ref "R16") (pin "1") (pinfunction "1_1") (pintype "passive"))
    )
    (net (code "11") (name "Net-(C37-Pad2)") (class "Default")
      (node (ref "C37") (pin "2") (pinfunction "2_2") (pintype "passive"))
      (node (ref "R23") (pin "1") (pinfunction "1_1") (pintype "passive"))
    )
    (net (code "12") (name "Net-(C38-Pad2)") (class "Default")
      (node (ref "C38") (pin "2") (pinfunction "2_2") (pintype "passive"))
      (node (ref "R25") (pin "1") (pinfunction "1_1") (pintype "passive"))
    )
    (net (code "13") (name "Net-(C44-Pad2)") (class "Default")
      (node (ref "C44") (pin "2") (pinfunction "2_2") (pintype "passive"))
      (node (ref "R34") (pin "1") (pinfunction "1_1") (pintype "passive"))
    )
    (net (code "14") (name "Net-(C45-Pad2)") (class "Default")
      (node (ref "C45") (pin "2") (pinfunction "2_2") (pintype "passive"))
      (node (ref "R35") (pin "1") (pinfunction "1_1") (pintype "passive"))
    )
    (net (code "15") (name "Net-(C49-Pad2)") (class "Default")
      (node (ref "C49") (pin "2") (pinfunction "2_2") (pintype "passive"))
      (node (ref "R40") (pin "1") (pinfunction "1_1") (pintype "passive"))
    )
    (net (code "16") (name "Net-(C51-Pad2)") (class "Default")
      (node (ref "C51") (pin "2") (pinfunction "2_2") (pintype "passive"))
      (node (ref "R44") (pin "1") (pinfunction "1_1") (pintype "passive"))
    )
    (net (code "17") (name "Net-(D1-K)") (class "Default")
      (node (ref "D1") (pin "1") (pinfunction "K_1") (pintype "passive"))
      (node (ref "R17") (pin "2") (pinfunction "2_2") (pintype "passive"))
    )
    (net (code "18") (name "Net-(D2-K)") (class "Default")
      (node (ref "D2") (pin "1") (pinfunction "K_1") (pintype "passive"))
      (node (ref "R18") (pin "2") (pinfunction "2_2") (pintype "passive"))
    )
    (net (code "19") (name "Net-(D3-K)") (class "Default")
      (node (ref "D3") (pin "1") (pinfunction "K_1") (pintype "passive"))
      (node (ref "R36") (pin "2") (pinfunction "2_2") (pintype "passive"))
    )
    (net (code "20") (name "Net-(D4-K)") (class "Default")
      (node (ref "D4") (pin "1") (pinfunction "K_1") (pintype "passive"))
      (node (ref "R37") (pin "2") (pinfunction "2_2") (pintype "passive"))
    )
    (net (code "21") (name "Net-(MIC1-A)") (class "Default")
      (node (ref "C29") (pin "1") (pinfunction "1_1") (pintype "passive"))
      (node (ref "C31") (pin "1") (pinfunction "1_1") (pintype "passive"))
      (node (ref "MIC1") (pin "1") (pinfunction "A_1") (pintype "passive"))
      (node (ref "R11") (pin "3") (pinfunction "3_3") (pintype "passive"))
      (node (ref "R12") (pin "1") (pinfunction "1_1") (pintype "passive"))
    )
    (net (code "22") (name "Net-(MIC2-A)") (class "Default")
      (node (ref "C30") (pin "1") (pinfunction "1_1") (pintype "passive"))
      (node (ref "C32") (pin "1") (pinfunction "1_1") (pintype "passive"))
      (node (ref "MIC2") (pin "1") (pinfunction "A_1") (pintype "passive"))
      (node (ref "R13") (pin "3") (pinfunction "3_3") (pintype "passive"))
      (node (ref "R14") (pin "1") (pinfunction "1_1") (pintype "passive"))
    )
    (net (code "23") (name "Net-(MIC3-A)") (class "Default")
      (node (ref "C43") (pin "1") (pinfunction "1_1") (pintype "passive"))
      (node (ref "C45") (pin "1") (pinfunction "1_1") (pintype "passive"))
      (node (ref "MIC3") (pin "1") (pinfunction "A_1") (pintype "passive"))
      (node (ref "R32") (pin "3") (pinfunction "3_3") (pintype "passive"))
      (node (ref "R33") (pin "1") (pinfunction "1_1") (pintype "passive"))
    )
    (net (code "24") (name "Net-(MIC4-A)") (class "Default")
      (node (ref "C42") (pin "1") (pinfunction "1_1") (pintype "passive"))
      (node (ref "C44") (pin "1") (pinfunction "1_1") (pintype "passive"))
      (node (ref "MIC4") (pin "1") (pinfunction "A_1") (pintype "passive"))
      (node (ref "R30") (pin "3") (pinfunction "3_3") (pintype "passive"))
      (node (ref "R31") (pin "1") (pinfunction "1_1") (pintype "passive"))
    )
    (net (code "25") (name "Net-(Q1-B)") (class "Default")
      (node (ref "Q1") (pin "1") (pinfunction "B_1") (pintype "passive"))
      (node (ref "R21") (pin "2") (pinfunction "2_2") (pintype "passive"))
    )
    (net (code "26") (name "Net-(Q1-C)") (class "Default")
      (node (ref "Q1") (pin "3") (pinfunction "C_3") (pintype "passive"))
      (node (ref "R19") (pin "1") (pinfunction "1_1") (pintype "passive"))
    )
    (net (code "27") (name "Net-(Q2-B)") (class "Default")
      (node (ref "Q2") (pin "1") (pinfunction "B_1") (pintype "passive"))
      (node (ref "R22") (pin "2") (pinfunction "2_2") (pintype "passive"))
    )
    (net (code "28") (name "Net-(Q2-C)") (class "Default")
      (node (ref "Q2") (pin "3") (pinfunction "C_3") (pintype "passive"))
      (node (ref "R20") (pin "1") (pinfunction "1_1") (pintype "passive"))
    )
    (net (code "29") (name "Net-(Q3-B)") (class "Default")
      (node (ref "Q3") (pin "1") (pinfunction "B_1") (pintype "passive"))
      (node (ref "R42") (pin "2") (pinfunction "2_2") (pintype "passive"))
    )
    (net (code "30") (name "Net-(Q3-C)") (class "Default")
      (node (ref "Q3") (pin "3") (pinfunction "C_3") (pintype "passive"))
      (node (ref "R38") (pin "1") (pinfunction "1_1") (pintype "passive"))
    )
    (net (code "31") (name "Net-(Q4-B)") (class "Default")
      (node (ref "Q4") (pin "1") (pinfunction "B_1") (pintype "passive"))
      (node (ref "R43") (pin "2") (pinfunction "2_2") (pintype "passive"))
    )
    (net (code "32") (name "Net-(Q4-C)") (class "Default")
      (node (ref "Q4") (pin "3") (pinfunction "C_3") (pintype "passive"))
      (node (ref "R39") (pin "1") (pinfunction "1_1") (pintype "passive"))
    )
    (net (code "33") (name "Net-(U4A-1IN+)") (class "Default")
      (node (ref "C27") (pin "1") (pinfunction "1_1") (pintype "passive"))
      (node (ref "R15") (pin "2") (pinfunction "2_2") (pintype "passive"))
      (node (ref "R9") (pin "1") (pinfunction "1_1") (pintype "passive"))
      (node (ref "U4") (pin "3") (pinfunction "1IN+_3") (pintype "tri_state"))
    )
    (net (code "34") (name "Net-(U4A-1IN-)") (class "Default")
      (node (ref "C35") (pin "1") (pinfunction "1_1") (pintype "passive"))
      (node (ref "R23") (pin "2") (pinfunction "2_2") (pintype "passive"))
      (node (ref "R24") (pin "1") (pinfunction "1_1") (pintype "passive"))
      (node (ref "U4") (pin "2") (pinfunction "1IN-_2") (pintype "tri_state"))
    )
    (net (code "35") (name "Net-(U4A-OUT)") (class "Default")
      (node (ref "C35") (pin "2") (pinfunction "2_2") (pintype "passive"))
      (node (ref "R17") (pin "1") (pinfunction "1_1") (pintype "passive"))
      (node (ref "R24") (pin "2") (pinfunction "2_2") (pintype "passive"))
      (node (ref "U4") (pin "1") (pinfunction "OUT_1") (pintype "output"))
    )
    (net (code "36") (name "Net-(U4A-VCC+)") (class "Default")
      (node (ref "C26") (pin "1") (pinfunction "1_1") (pintype "passive"))
      (node (ref "R8") (pin "1") (pinfunction "1_1") (pintype "passive"))
      (node (ref "U4") (pin "8") (pinfunction "VCC+_8") (pintype "power_in"))
    )
    (net (code "37") (name "Net-(U4B-1IN+)") (class "Default")
      (node (ref "C28") (pin "1") (pinfunction "1_1") (pintype "passive"))
      (node (ref "R10") (pin "1") (pinfunction "1_1") (pintype "passive"))
      (node (ref "R16") (pin "2") (pinfunction "2_2") (pintype "passive"))
      (node (ref "U4") (pin "5") (pinfunction "1IN+_5") (pintype "tri_state"))
    )
    (net (code "38") (name "Net-(U4B-1IN-)") (class "Default")
      (node (ref "C36") (pin "1") (pinfunction "1_1") (pintype "passive"))
      (node (ref "R25") (pin "2") (pinfunction "2_2") (pintype "passive"))
      (node (ref "R26") (pin "1") (pinfunction "1_1") (pintype "passive"))
      (node (ref "U4") (pin "6") (pinfunction "1IN-_6") (pintype "tri_state"))
    )
    (net (code "39") (name "Net-(U4B-OUT)") (class "Default")
      (node (ref "C36") (pin "2") (pinfunction "2_2") (pintype "passive"))
      (node (ref "R18") (pin "1") (pinfunction "1_1") (pintype "passive"))
      (node (ref "R26") (pin "2") (pinfunction "2_2") (pintype "passive"))
      (node (ref "U4") (pin "7") (pinfunction "OUT_7") (pintype "output"))
    )
    (net (code "40") (name "Net-(U5A-1IN+)") (class "Default")
      (node (ref "C41") (pin "1") (pinfunction "1_1") (pintype "passive"))
      (node (ref "R29") (pin "1") (pinfunction "1_1") (pintype "passive"))
      (node (ref "R35") (pin "2") (pinfunction "2_2") (pintype "passive"))
      (node (ref "U5") (pin "3") (pinfunction "1IN+_3") (pintype "tri_state"))
    )
    (net (code "41") (name "Net-(U5A-1IN-)") (class "Default")
      (node (ref "C50") (pin "1") (pinfunction "1_1") (pintype "passive"))
      (node (ref "R44") (pin "2") (pinfunction "2_2") (pintype "passive"))
      (node (ref "R45") (pin "1") (pinfunction "1_1") (pintype "passive"))
      (node (ref "U5") (pin "2") (pinfunction "1IN-_2") (pintype "tri_state"))
    )
    (net (code "42") (name "Net-(U5A-OUT)") (class "Default")
      (node (ref "C50") (pin "2") (pinfunction "2_2") (pintype "passive"))
      (node (ref "R37") (pin "1") (pinfunction "1_1") (pintype "passive"))
      (node (ref "R45") (pin "2") (pinfunction "2_2") (pintype "passive"))
      (node (ref "U5") (pin "1") (pinfunction "OUT_1") (pintype "output"))
    )
    (net (code "43") (name "Net-(U5A-VCC+)") (class "Default")
      (node (ref "C40") (pin "1") (pinfunction "1_1") (pintype "passive"))
      (node (ref "R27") (pin "1") (pinfunction "1_1") (pintype "passive"))
      (node (ref "U5") (pin "8") (pinfunction "VCC+_8") (pintype "power_in"))
    )
    (net (code "44") (name "Net-(U5B-1IN+)") (class "Default")
      (node (ref "C39") (pin "1") (pinfunction "1_1") (pintype "passive"))
      (node (ref "R28") (pin "1") (pinfunction "1_1") (pintype "passive"))
      (node (ref "R34") (pin "2") (pinfunction "2_2") (pintype "passive"))
      (node (ref "U5") (pin "5") (pinfunction "1IN+_5") (pintype "tri_state"))
    )
    (net (code "45") (name "Net-(U5B-1IN-)") (class "Default")
      (node (ref "C46") (pin "1") (pinfunction "1_1") (pintype "passive"))
      (node (ref "R40") (pin "2") (pinfunction "2_2") (pintype "passive"))
      (node (ref "R41") (pin "1") (pinfunction "1_1") (pintype "passive"))
      (node (ref "U5") (pin "6") (pinfunction "1IN-_6") (pintype "tri_state"))
    )
    (net (code "46") (name "Net-(U5B-OUT)") (class "Default")
      (node (ref "C46") (pin "2") (pinfunction "2_2") (pintype "passive"))
      (node (ref "R36") (pin "1") (pinfunction "1_1") (pintype "passive"))
      (node (ref "R41") (pin "2") (pinfunction "2_2") (pintype "passive"))
      (node (ref "U5") (pin "7") (pinfunction "OUT_7") (pintype "output"))
    )
  )
)
